# Voltmeter_Schematic.net
KiCad netlist of a schematic drawn in Altium Designer
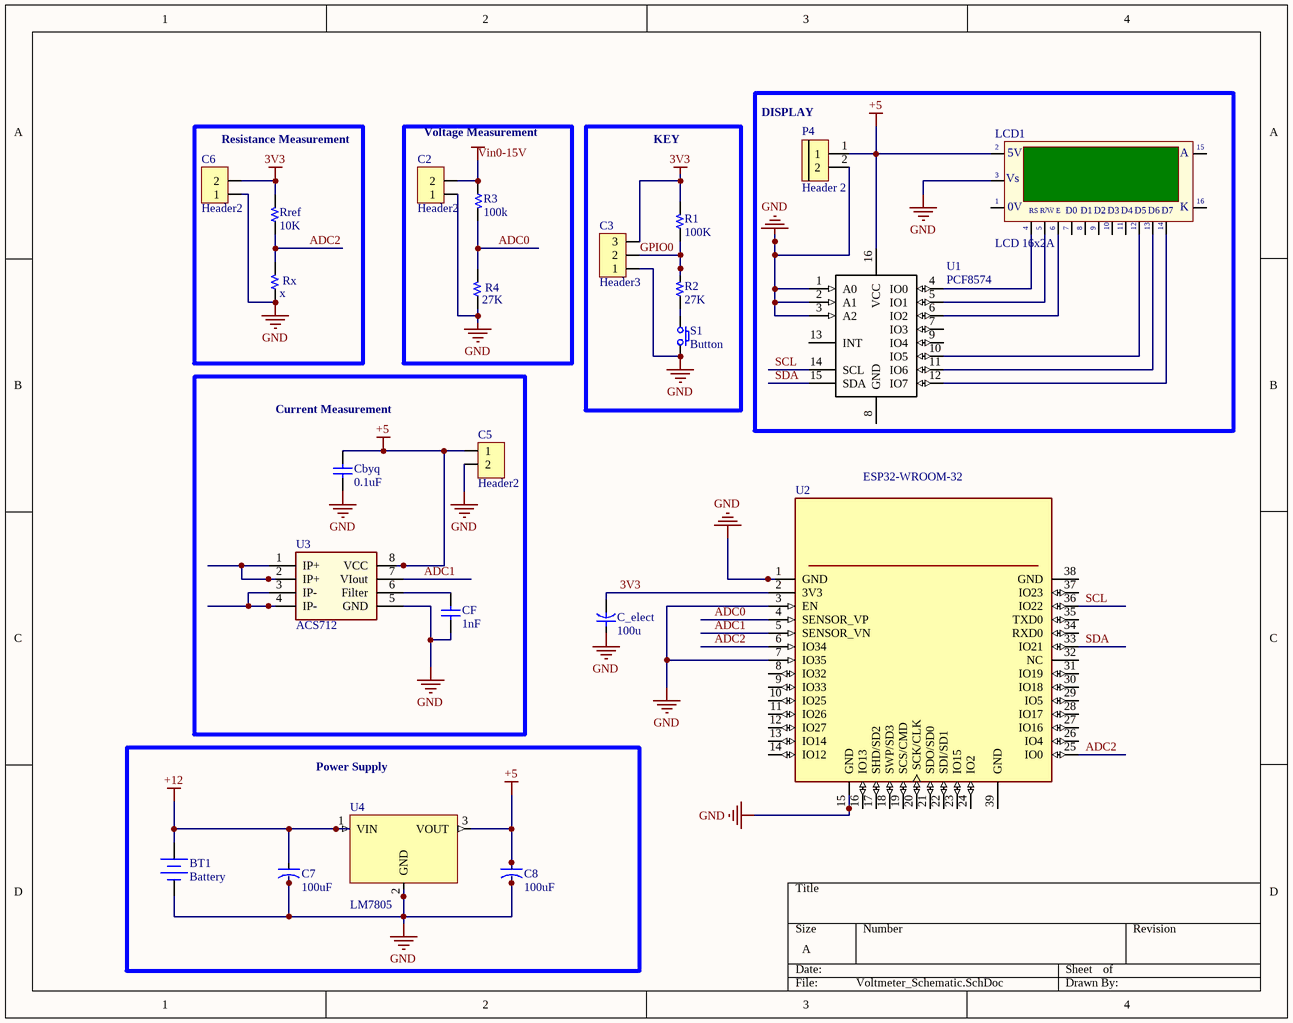
[diagram p0: Voltmeter_Schematic.SchDoc]

(export (version "E")
  (design (tool "Eeschema 10.0.6"))
  (components
    (comp (ref "BT1")
      (value "Battery")
      (footprint "CON CR1220")
      (libsource (lib "chipfc_libs") (part "Battery"))
    )
    (comp (ref "C2")
      (value "Header2")
      (footprint "HDR2")
      (description "Header IDC, 2 x 1 Pin Vertical 2.54mm Pitch (Non-Boxed, Male)")
      (fields
        (field (name "MANUFACTURER") "Würth Elektronik eiSos GmbH")
        (field (name "PARTNO") "613002143121")
        (field (name "CREATED BY") "Karrer Zheng")
      )
      (libsource (lib "LIBRARY") (part "Header2"))
    )
    (comp (ref "C3")
      (value "Header3")
      (footprint "HDR3")
      (description "Header IDC, 3 x 1 Pin Vertical 2.54mm Pitch (Non-Boxed, Male)")
      (fields
        (field (name "MANUFACTURER") "Würth Elektronik eiSos GmbH")
        (field (name "PARTNO") "613002143121")
        (field (name "CREATED BY") "Karrer Zheng")
      )
      (libsource (lib "LIBRARY") (part "Header3"))
    )
    (comp (ref "C5")
      (value "Header2")
      (footprint "HDR2")
      (description "Header IDC, 2 x 1 Pin Vertical 2.54mm Pitch (Non-Boxed, Male)")
      (fields
        (field (name "MANUFACTURER") "Würth Elektronik eiSos GmbH")
        (field (name "PARTNO") "613002143121")
        (field (name "CREATED BY") "Karrer Zheng")
      )
      (libsource (lib "") (part "Header2_1"))
    )
    (comp (ref "C6")
      (value "Header2")
      (footprint "HDR2")
      (description "Header IDC, 2 x 1 Pin Vertical 2.54mm Pitch (Non-Boxed, Male)")
      (fields
        (field (name "MANUFACTURER") "Würth Elektronik eiSos GmbH")
        (field (name "PARTNO") "613002143121")
        (field (name "CREATED BY") "Karrer Zheng")
      )
      (libsource (lib "LIBRARY") (part "Header2"))
    )
    (comp (ref "C7")
      (value "100uF")
      (footprint "CA-ALU-2.54")
      (description "Capacitor (Semiconductor SIM Model)")
      (fields (field (name "PUBLISHER") "Altium Limited"))
      (libsource (lib "LIBRARY") (part "CN-ALU-DIP"))
    )
    (comp (ref "C8")
      (value "100uF")
      (footprint "CA-ALU-2.54")
      (description "Capacitor (Semiconductor SIM Model)")
      (fields (field (name "PUBLISHER") "Altium Limited"))
      (libsource (lib "LIBRARY") (part "CN-ALU-DIP"))
    )
    (comp (ref "Cbyq")
      (value "0.1uF")
      (footprint "C 0805")
      (description "Capacitor non-pol")
      (libsource (lib "chipfc_libs") (part "Capacitor NP"))
    )
    (comp (ref "CF")
      (value "1nF")
      (footprint "C 0805")
      (description "Capacitor non-pol")
      (libsource (lib "chipfc_libs") (part "Capacitor NP"))
    )
    (comp (ref "C_elect")
      (value "100u")
      (footprint "C Super Case A")
      (description "Capacitor pol")
      (libsource (lib "chipfc_libs") (part "Capacitor"))
    )
    (comp (ref "LCD1")
      (value "LCD 16x2A")
      (footprint "JP16-C1T")
      (description "LCD dipslay 16 char, 2 line")
      (libsource (lib "LIBRARY") (part "LCD16x2A"))
    )
    (comp (ref "P4")
      (value "Header 2")
      (footprint "BIG_Header 2")
      (description "Big Header 2")
      (libsource (lib "Cty1") (part "Header 2"))
    )
    (comp (ref "R1")
      (value "100K")
      (footprint "R 0805")
      (description "Resistor")
      (libsource (lib "chipfc_libs") (part "Resistor"))
    )
    (comp (ref "R2")
      (value "27K")
      (footprint "R 0805")
      (description "Resistor")
      (libsource (lib "chipfc_libs") (part "Resistor"))
    )
    (comp (ref "R3")
      (value "100k")
      (footprint "R 0805")
      (description "Resistor")
      (libsource (lib "chipfc_libs") (part "Resistor"))
    )
    (comp (ref "R4")
      (value "27K")
      (footprint "R 0805")
      (description "Resistor")
      (libsource (lib "chipfc_libs") (part "Resistor"))
    )
    (comp (ref "Rref")
      (value "10K")
      (footprint "R 0805")
      (description "Resistor")
      (libsource (lib "chipfc_libs") (part "Resistor"))
    )
    (comp (ref "Rx")
      (value "x")
      (footprint "R 0805")
      (description "Resistor")
      (libsource (lib "chipfc_libs") (part "Resistor"))
    )
    (comp (ref "S1")
      (value "Button")
      (footprint "SW/2/DIP")
      (description "Tact switch 2 pin")
      (libsource (lib "chipfc_libs") (part "SW SPST"))
    )
    (comp (ref "U1")
      (value "PCF8574")
      (footprint "DIP16")
      (description "I2C PORT EXPANDER")
      (fields
        (field (name "MANUFACTURER PART NUMBER") "PCF8574T/3,512")
        (field (name "MANUFACTURER") "NXP Semiconductors")
      )
      (libsource (lib "LIBRARY") (part "PCF8574"))
    )
    (comp (ref "U2")
      (value "ESP32-WROOM-32")
      (footprint "MODULE_ESP32-WROOM-32")
      (fields (field (name "MF") "Espressif Systems") (field (name "MP") "ESP32-WROOM-32D"))
      (libsource (lib "ESP32") (part "ESP32-WROOM-32"))
    )
    (comp (ref "U3") (value "ACS712") (footprint "SOIC-8") (libsource (lib "chipfc_libs") (part "ACS712")))
    (comp (ref "U4")
      (value "LM7805")
      (footprint "TO-220")
      (description "TO-220")
      (libsource (lib "Cty1") (part "LM7805"))
    )
  )
  (nets
    (net (code "1") (name "+5") (class "Default")
      (node (ref "C5") (pin "1") (pinfunction "1_1") (pintype "passive"))
      (node (ref "C8") (pin "1") (pinfunction "1_1") (pintype "passive"))
      (node (ref "Cbyq") (pin "1") (pinfunction "1_1") (pintype "passive"))
      (node (ref "LCD1") (pin "2") (pinfunction "VDD_2") (pintype "passive"))
      (node (ref "P4") (pin "1") (pinfunction "1_1") (pintype "passive"))
      (node (ref "U1") (pin "16") (pinfunction "VCC_16") (pintype "passive"))
      (node (ref "U3") (pin "8") (pinfunction "VCC_8") (pintype "passive"))
      (node (ref "U4") (pin "3") (pinfunction "VOUT_3") (pintype "output"))
    )
    (net (code "2") (name "+12") (class "Default")
      (node (ref "BT1") (pin "1") (pinfunction "V+_1") (pintype "passive"))
      (node (ref "C7") (pin "1") (pinfunction "1_1") (pintype "passive"))
      (node (ref "U4") (pin "1") (pinfunction "VIN_1") (pintype "input"))
    )
    (net (code "3") (name "/ADC0") (class "Default")
      (node (ref "R3") (pin "2") (pinfunction "2_2") (pintype "passive"))
      (node (ref "R4") (pin "2") (pinfunction "2_2") (pintype "passive"))
      (node (ref "U2") (pin "4") (pinfunction "SENSOR_VP_4") (pintype "input"))
    )
    (net (code "4") (name "/ADC1") (class "Default")
      (node (ref "U2") (pin "5") (pinfunction "SENSOR_VN_5") (pintype "input"))
      (node (ref "U3") (pin "7") (pinfunction "VIout_7") (pintype "passive"))
    )
    (net (code "5") (name "/ADC2") (class "Default")
      (node (ref "Rref") (pin "1") (pinfunction "1_1") (pintype "passive"))
      (node (ref "Rx") (pin "2") (pinfunction "2_2") (pintype "passive"))
      (node (ref "U2") (pin "25") (pinfunction "IO0_25") (pintype "bidirectional"))
      (node (ref "U2") (pin "6") (pinfunction "IO34_6") (pintype "input"))
    )
    (net (code "6") (name "/GPIO0") (class "Default")
      (node (ref "C3") (pin "2") (pinfunction "2_2") (pintype "passive"))
      (node (ref "R1") (pin "1") (pinfunction "1_1") (pintype "passive"))
      (node (ref "R2") (pin "2") (pinfunction "2_2") (pintype "passive"))
    )
    (net (code "7") (name "/SCL") (class "Default")
      (node (ref "U1") (pin "14") (pinfunction "SCL_14") (pintype "open_collector"))
      (node (ref "U2") (pin "36") (pinfunction "IO22_36") (pintype "bidirectional"))
    )
    (net (code "8") (name "/SDA") (class "Default")
      (node (ref "U1") (pin "15") (pinfunction "SDA_15") (pintype "open_collector"))
      (node (ref "U2") (pin "33") (pinfunction "IO21_33") (pintype "bidirectional"))
    )
    (net (code "9") (name "/Vin0-15V") (class "Default")
      (node (ref "C2") (pin "2") (pinfunction "2_2") (pintype "passive"))
      (node (ref "R3") (pin "1") (pinfunction "1_1") (pintype "passive"))
    )
    (net (code "10") (name "3V3") (class "Default")
      (node (ref "C3") (pin "3") (pinfunction "3_3") (pintype "passive"))
      (node (ref "C6") (pin "2") (pinfunction "2_2") (pintype "passive"))
      (node (ref "C_elect") (pin "2") (pinfunction "2_2") (pintype "passive"))
      (node (ref "R1") (pin "2") (pinfunction "2_2") (pintype "passive"))
      (node (ref "Rref") (pin "2") (pinfunction "2_2") (pintype "passive"))
      (node (ref "U2") (pin "2") (pinfunction "3V3_2") (pintype "power_in"))
    )
    (net (code "11") (name "GND") (class "Default")
      (node (ref "BT1") (pin "2") (pinfunction "V-_2") (pintype "passive"))
      (node (ref "C2") (pin "1") (pinfunction "1_1") (pintype "passive"))
      (node (ref "C3") (pin "1") (pinfunction "1_1") (pintype "passive"))
      (node (ref "C5") (pin "2") (pinfunction "2_2") (pintype "passive"))
      (node (ref "C6") (pin "1") (pinfunction "1_1") (pintype "passive"))
      (node (ref "C7") (pin "2") (pinfunction "2_2") (pintype "passive"))
      (node (ref "C8") (pin "2") (pinfunction "2_2") (pintype "passive"))
      (node (ref "CF") (pin "2") (pinfunction "2_2") (pintype "passive"))
      (node (ref "Cbyq") (pin "2") (pinfunction "2_2") (pintype "passive"))
      (node (ref "LCD1") (pin "3") (pinfunction "VEE_3") (pintype "passive"))
      (node (ref "P4") (pin "2") (pinfunction "2_2") (pintype "passive"))
      (node (ref "R4") (pin "1") (pinfunction "1_1") (pintype "passive"))
      (node (ref "Rx") (pin "1") (pinfunction "1_1") (pintype "passive"))
      (node (ref "S1") (pin "2") (pinfunction "2_2") (pintype "passive"))
      (node (ref "U1") (pin "1") (pinfunction "A0_1") (pintype "input"))
      (node (ref "U1") (pin "2") (pinfunction "A1_2") (pintype "input"))
      (node (ref "U1") (pin "3") (pinfunction "A2_3") (pintype "input"))
      (node (ref "U2") (pin "1") (pinfunction "GND_1") (pintype "power_in"))
      (node (ref "U2") (pin "15") (pinfunction "GND_15") (pintype "power_in"))
      (node (ref "U2") (pin "3") (pinfunction "EN_3") (pintype "input"))
      (node (ref "U2") (pin "7") (pinfunction "IO35_7") (pintype "input"))
      (node (ref "U3") (pin "5") (pinfunction "GND_5") (pintype "passive"))
      (node (ref "U4") (pin "2") (pinfunction "GND_2") (pintype "power_in"))
    )
    (net (code "12") (name "Net-(LCD1-D5)") (class "Default")
      (node (ref "LCD1") (pin "12") (pinfunction "D5_12") (pintype "passive"))
      (node (ref "U1") (pin "10") (pinfunction "IO5_10") (pintype "bidirectional"))
    )
    (net (code "13") (name "Net-(LCD1-D6)") (class "Default")
      (node (ref "LCD1") (pin "13") (pinfunction "D6_13") (pintype "passive"))
      (node (ref "U1") (pin "11") (pinfunction "IO6_11") (pintype "bidirectional"))
    )
    (net (code "14") (name "Net-(LCD1-D7)") (class "Default")
      (node (ref "LCD1") (pin "14") (pinfunction "D7_14") (pintype "passive"))
      (node (ref "U1") (pin "12") (pinfunction "IO7_12") (pintype "bidirectional"))
    )
    (net (code "15") (name "Net-(LCD1-RS)") (class "Default")
      (node (ref "LCD1") (pin "4") (pinfunction "RS_4") (pintype "passive"))
      (node (ref "U1") (pin "4") (pinfunction "IO0_4") (pintype "bidirectional"))
    )
    (net (code "16") (name "Net-(LCD1-R{slash}~{W})") (class "Default")
      (node (ref "LCD1") (pin "5") (pinfunction "R/~{W}_5") (pintype "passive"))
      (node (ref "U1") (pin "5") (pinfunction "IO1_5") (pintype "bidirectional"))
    )
    (net (code "17") (name "Net-(LCD1-~{EN})") (class "Default")
      (node (ref "LCD1") (pin "6") (pinfunction "~{EN}_6") (pintype "passive"))
      (node (ref "U1") (pin "6") (pinfunction "IO2_6") (pintype "bidirectional"))
    )
    (net (code "18") (name "Net-(R2-Pad1)") (class "Default")
      (node (ref "R2") (pin "1") (pinfunction "1_1") (pintype "passive"))
      (node (ref "S1") (pin "1") (pinfunction "1_1") (pintype "passive"))
    )
    (net (code "19") (name "Net-(U3-Filter)") (class "Default")
      (node (ref "CF") (pin "1") (pinfunction "1_1") (pintype "passive"))
      (node (ref "U3") (pin "6") (pinfunction "Filter_6") (pintype "passive"))
    )
    (net (code "20") (name "Net-(U3-IP+-Pad1)") (class "Default")
      (node (ref "U3") (pin "1") (pinfunction "IP+_1") (pintype "passive"))
      (node (ref "U3") (pin "2") (pinfunction "IP+_2") (pintype "passive"))
    )
    (net (code "21") (name "Net-(U3-IP--Pad3)") (class "Default")
      (node (ref "U3") (pin "3") (pinfunction "IP-_3") (pintype "passive"))
      (node (ref "U3") (pin "4") (pinfunction "IP-_4") (pintype "passive"))
    )
    (net (code "22") (name "unconnected-(C_elect-Pad1)") (class "Default")
      (node (ref "C_elect") (pin "1") (pinfunction "1_1") (pintype "passive"))
    )
    (net (code "23") (name "unconnected-(LCD1-A-Pad15)") (class "Default")
      (node (ref "LCD1") (pin "15") (pinfunction "A_15") (pintype "passive"))
    )
    (net (code "24") (name "unconnected-(LCD1-D0-Pad7)") (class "Default")
      (node (ref "LCD1") (pin "7") (pinfunction "D0_7") (pintype "passive"))
    )
    (net (code "25") (name "unconnected-(LCD1-D1-Pad8)") (class "Default")
      (node (ref "LCD1") (pin "8") (pinfunction "D1_8") (pintype "passive"))
    )
    (net (code "26") (name "unconnected-(LCD1-D2-Pad9)") (class "Default")
      (node (ref "LCD1") (pin "9") (pinfunction "D2_9") (pintype "passive"))
    )
    (net (code "27") (name "unconnected-(LCD1-D3-Pad10)") (class "Default")
      (node (ref "LCD1") (pin "10") (pinfunction "D3_10") (pintype "passive"))
    )
    (net (code "28") (name "unconnected-(LCD1-D4-Pad11)") (class "Default")
      (node (ref "LCD1") (pin "11") (pinfunction "D4_11") (pintype "passive"))
    )
    (net (code "29") (name "unconnected-(LCD1-GND-Pad1)") (class "Default")
      (node (ref "LCD1") (pin "1") (pinfunction "GND_1") (pintype "passive"))
    )
    (net (code "30") (name "unconnected-(LCD1-K-Pad16)") (class "Default")
      (node (ref "LCD1") (pin "16") (pinfunction "K_16") (pintype "passive"))
    )
    (net (code "31") (name "unconnected-(U1-GND-Pad8)") (class "Default")
      (node (ref "U1") (pin "8") (pinfunction "GND_8") (pintype "open_collector"))
    )
    (net (code "32") (name "unconnected-(U1-INT-Pad13)") (class "Default")
      (node (ref "U1") (pin "13") (pinfunction "INT_13") (pintype "open_collector"))
    )
    (net (code "33") (name "unconnected-(U1-IO3-Pad7)") (class "Default")
      (node (ref "U1") (pin "7") (pinfunction "IO3_7") (pintype "bidirectional"))
    )
    (net (code "34") (name "unconnected-(U1-IO4-Pad9)") (class "Default")
      (node (ref "U1") (pin "9") (pinfunction "IO4_9") (pintype "bidirectional"))
    )
    (net (code "35") (name "unconnected-(U2-GND-Pad38)") (class "Default")
      (node (ref "U2") (pin "38") (pinfunction "GND_38") (pintype "power_in"))
    )
    (net (code "36") (name "unconnected-(U2-GND-Pad39)") (class "Default")
      (node (ref "U2") (pin "39") (pinfunction "GND_39") (pintype "power_in"))
    )
    (net (code "37") (name "unconnected-(U2-IO2-Pad24)") (class "Default")
      (node (ref "U2") (pin "24") (pinfunction "IO2_24") (pintype "bidirectional"))
    )
    (net (code "38") (name "unconnected-(U2-IO4-Pad26)") (class "Default")
      (node (ref "U2") (pin "26") (pinfunction "IO4_26") (pintype "bidirectional"))
    )
    (net (code "39") (name "unconnected-(U2-IO5-Pad29)") (class "Default")
      (node (ref "U2") (pin "29") (pinfunction "IO5_29") (pintype "bidirectional"))
    )
    (net (code "40") (name "unconnected-(U2-IO12-Pad14)") (class "Default")
      (node (ref "U2") (pin "14") (pinfunction "IO12_14") (pintype "bidirectional"))
    )
    (net (code "41") (name "unconnected-(U2-IO13-Pad16)") (class "Default")
      (node (ref "U2") (pin "16") (pinfunction "IO13_16") (pintype "bidirectional"))
    )
    (net (code "42") (name "unconnected-(U2-IO14-Pad13)") (class "Default")
      (node (ref "U2") (pin "13") (pinfunction "IO14_13") (pintype "bidirectional"))
    )
    (net (code "43") (name "unconnected-(U2-IO15-Pad23)") (class "Default")
      (node (ref "U2") (pin "23") (pinfunction "IO15_23") (pintype "bidirectional"))
    )
    (net (code "44") (name "unconnected-(U2-IO16-Pad27)") (class "Default")
      (node (ref "U2") (pin "27") (pinfunction "IO16_27") (pintype "bidirectional"))
    )
    (net (code "45") (name "unconnected-(U2-IO17-Pad28)") (class "Default")
      (node (ref "U2") (pin "28") (pinfunction "IO17_28") (pintype "bidirectional"))
    )
    (net (code "46") (name "unconnected-(U2-IO18-Pad30)") (class "Default")
      (node (ref "U2") (pin "30") (pinfunction "IO18_30") (pintype "bidirectional"))
    )
    (net (code "47") (name "unconnected-(U2-IO19-Pad31)") (class "Default")
      (node (ref "U2") (pin "31") (pinfunction "IO19_31") (pintype "bidirectional"))
    )
    (net (code "48") (name "unconnected-(U2-IO23-Pad37)") (class "Default")
      (node (ref "U2") (pin "37") (pinfunction "IO23_37") (pintype "bidirectional"))
    )
    (net (code "49") (name "unconnected-(U2-IO25-Pad10)") (class "Default")
      (node (ref "U2") (pin "10") (pinfunction "IO25_10") (pintype "bidirectional"))
    )
    (net (code "50") (name "unconnected-(U2-IO26-Pad11)") (class "Default")
      (node (ref "U2") (pin "11") (pinfunction "IO26_11") (pintype "bidirectional"))
    )
    (net (code "51") (name "unconnected-(U2-IO27-Pad12)") (class "Default")
      (node (ref "U2") (pin "12") (pinfunction "IO27_12") (pintype "bidirectional"))
    )
    (net (code "52") (name "unconnected-(U2-IO32-Pad8)") (class "Default")
      (node (ref "U2") (pin "8") (pinfunction "IO32_8") (pintype "bidirectional"))
    )
    (net (code "53") (name "unconnected-(U2-IO33-Pad9)") (class "Default")
      (node (ref "U2") (pin "9") (pinfunction "IO33_9") (pintype "bidirectional"))
    )
    (net (code "54") (name "unconnected-(U2-NC-Pad32)") (class "Default")
      (node (ref "U2") (pin "32") (pinfunction "NC_32") (pintype "power_in"))
    )
    (net (code "55") (name "unconnected-(U2-RXD0-Pad34)") (class "Default")
      (node (ref "U2") (pin "34") (pinfunction "RXD0_34") (pintype "bidirectional"))
    )
    (net (code "56") (name "unconnected-(U2-SCK{slash}CLK-Pad20)") (class "Default")
      (node (ref "U2") (pin "20") (pinfunction "SCK/CLK_20") (pintype "bidirectional"))
    )
    (net (code "57") (name "unconnected-(U2-SCS{slash}CMD-Pad19)") (class "Default")
      (node (ref "U2") (pin "19") (pinfunction "SCS/CMD_19") (pintype "bidirectional"))
    )
    (net (code "58") (name "unconnected-(U2-SDI{slash}SD1-Pad22)") (class "Default")
      (node (ref "U2") (pin "22") (pinfunction "SDI/SD1_22") (pintype "bidirectional"))
    )
    (net (code "59") (name "unconnected-(U2-SDO{slash}SD0-Pad21)") (class "Default")
      (node (ref "U2") (pin "21") (pinfunction "SDO/SD0_21") (pintype "bidirectional"))
    )
    (net (code "60") (name "unconnected-(U2-SHD{slash}SD2-Pad17)") (class "Default")
      (node (ref "U2") (pin "17") (pinfunction "SHD/SD2_17") (pintype "bidirectional"))
    )
    (net (code "61") (name "unconnected-(U2-SWP{slash}SD3-Pad18)") (class "Default")
      (node (ref "U2") (pin "18") (pinfunction "SWP/SD3_18") (pintype "bidirectional"))
    )
    (net (code "62") (name "unconnected-(U2-TXD0-Pad35)") (class "Default")
      (node (ref "U2") (pin "35") (pinfunction "TXD0_35") (pintype "bidirectional"))
    )
  )
)
